# POE_plus_input.net
KiCad netlist of a schematic drawn in EAGLE
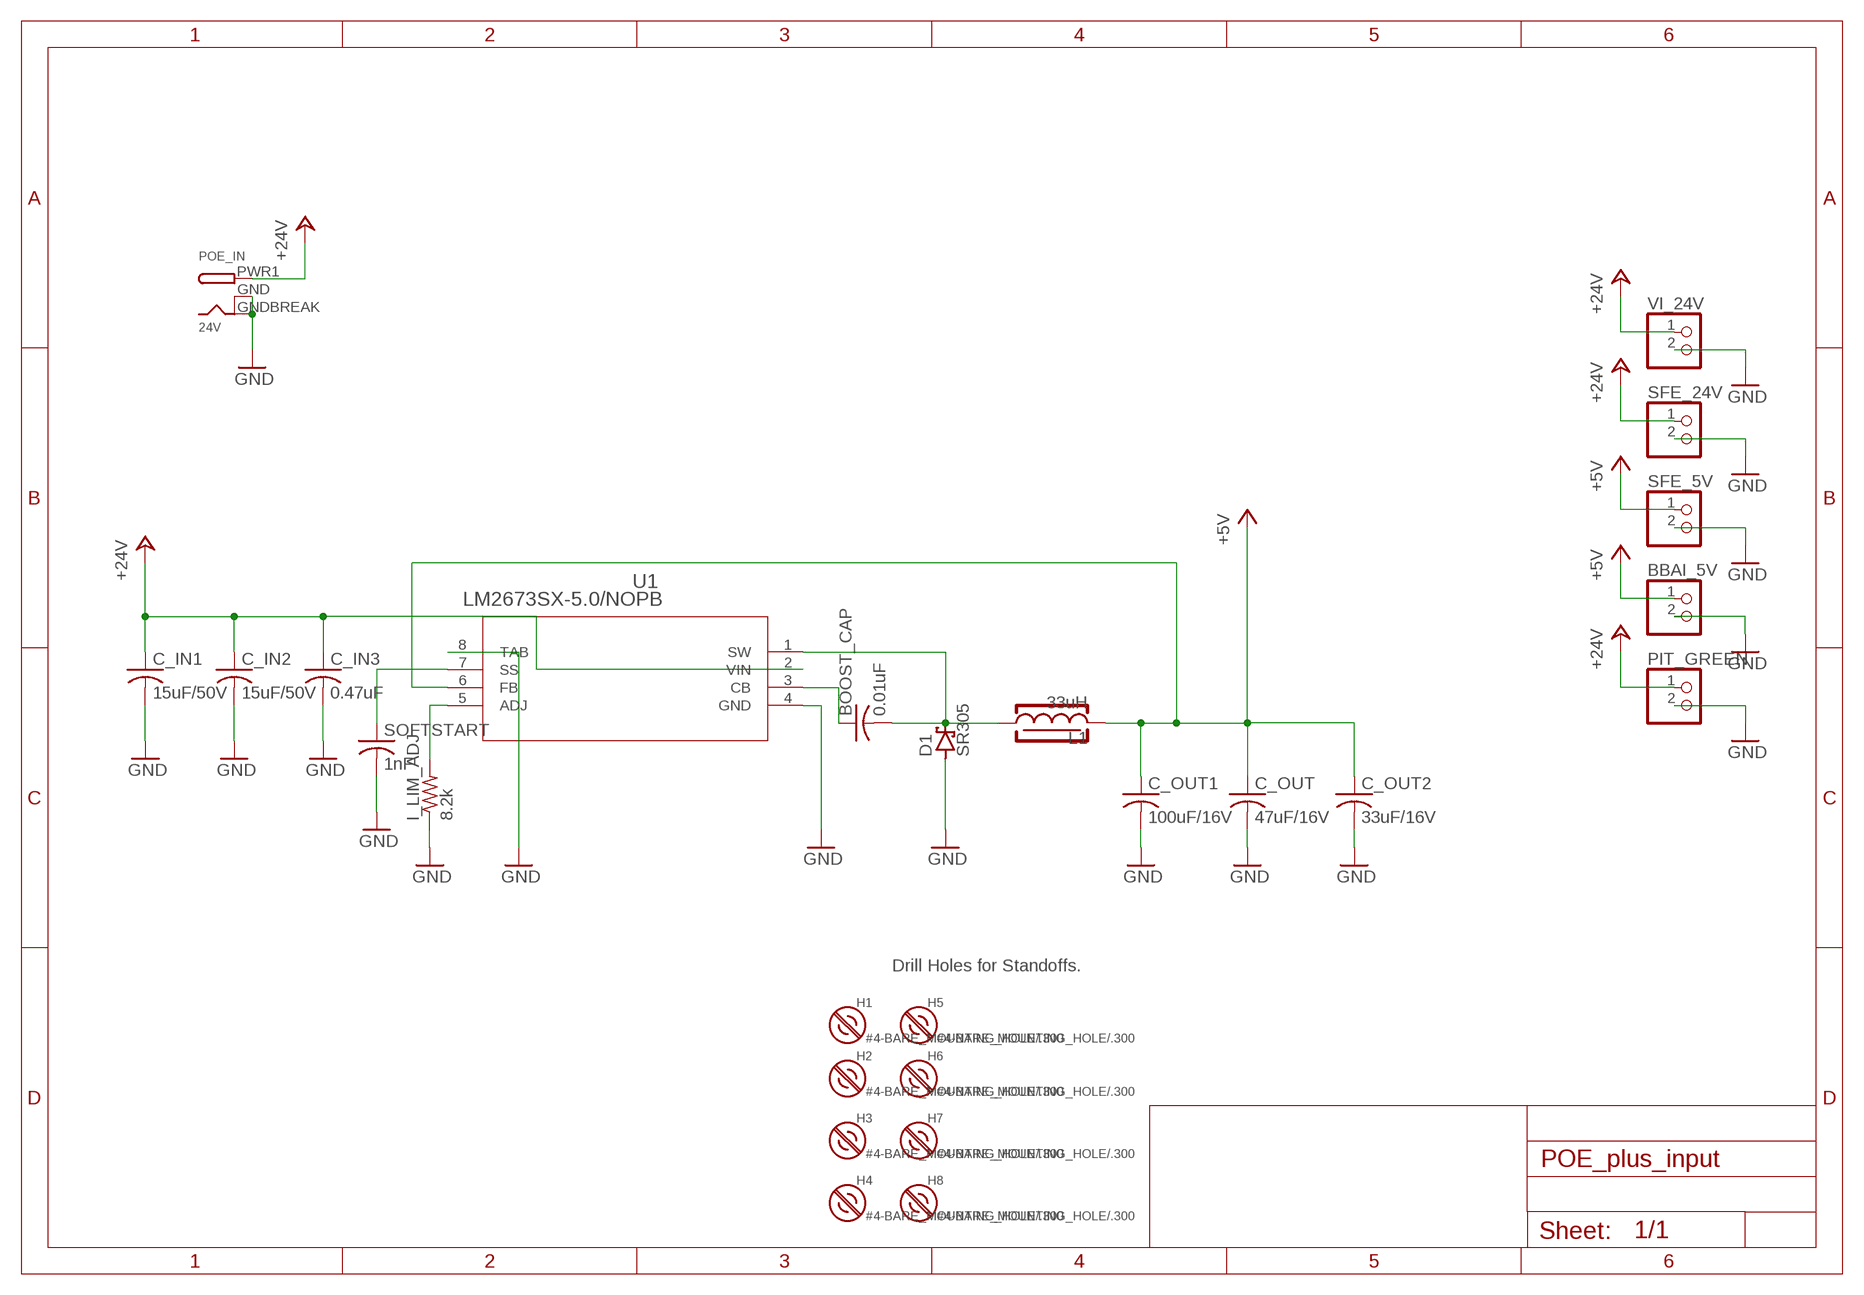
[diagram p0: schematic, sheet 1]

(export (version "E")
  (design (tool "Eeschema 10.0.6"))
  (components
    (comp (ref "BBAI_5V")
      (value "PINHD-1X2")
      (footprint "eagle-import:1X02")
      (fields (field (name "MFR") "Molex") (field (name "MPN") "1718573002"))
      (libsource (lib "eagle-import") (part "PINHD-1X2"))
    )
    (comp (ref "BOOST_CAP")
      (value "0.01uF")
      (footprint "eagle-import:C0805K")
      (fields (field (name "MFR") "AVX Corporation") (field (name "MPN") "06035C103JAT2A"))
      (libsource (lib "eagle-import") (part "C-USC0805K"))
    )
    (comp (ref "C_IN1")
      (value "15uF/50V")
      (footprint "eagle-import:C2220K")
      (fields (field (name "MFR") "United Chemi-Con") (field (name "MPN") "KTS500B156M55N0T00"))
      (libsource (lib "eagle-import") (part "C-USC2220K"))
    )
    (comp (ref "C_IN2")
      (value "15uF/50V")
      (footprint "eagle-import:C2220K")
      (fields (field (name "MFR") "United Chemi-Con") (field (name "MPN") "KTS500B156M55N0T00"))
      (libsource (lib "eagle-import") (part "C-USC2220K"))
    )
    (comp (ref "C_IN3")
      (value "0.47uF")
      (footprint "eagle-import:C0805K")
      (fields (field (name "MFR") "Taiyo Yuden") (field (name "MPN") "UMK107ABJ474KA-T"))
      (libsource (lib "eagle-import") (part "C-USC0805K"))
    )
    (comp (ref "C_OUT")
      (value "47uF/16V")
      (footprint "eagle-import:C1210K")
      (fields (field (name "MFR") "Murata Electronics") (field (name "MPN") "GRM32EC81C476KE15K"))
      (libsource (lib "eagle-import") (part "C-USC1210K"))
    )
    (comp (ref "C_OUT1")
      (value "100uF/16V")
      (footprint "eagle-import:C1210K")
      (fields (field (name "MFR") "Taiyo Yuden") (field (name "MPN") "EMK325ABJ107MM-P"))
      (libsource (lib "eagle-import") (part "C-USC1210K"))
    )
    (comp (ref "C_OUT2")
      (value "33uF/16V")
      (footprint "eagle-import:C1206K")
      (fields (field (name "MFR") "TDK Corporation") (field (name "MPN") "C3216X5R1C336M160AB"))
      (libsource (lib "eagle-import") (part "C-USC1206K"))
    )
    (comp (ref "D1")
      (value "SR305")
      (footprint "eagle-import:C4111-15")
      (fields (field (name "MFR") "Micro Commercial Co") (field (name "MPN") "SR305-TP"))
      (libsource (lib "eagle-import") (part "1N5908"))
    )
    (comp (ref "H1")
      (value "#4-BARE_MOUNTING_HOLE/.300")
      (footprint "eagle-import:#4_.300-BARE+STD_NUT_OR_STAR_WASHER")
      (libsource (lib "eagle-import") (part "#4-BARE_MOUNTING_HOLE/.300"))
    )
    (comp (ref "H2")
      (value "#4-BARE_MOUNTING_HOLE/.300")
      (footprint "eagle-import:#4_.300-BARE+STD_NUT_OR_STAR_WASHER")
      (libsource (lib "eagle-import") (part "#4-BARE_MOUNTING_HOLE/.300"))
    )
    (comp (ref "H3")
      (value "#4-BARE_MOUNTING_HOLE/.300")
      (footprint "eagle-import:#4_.300-BARE+STD_NUT_OR_STAR_WASHER")
      (libsource (lib "eagle-import") (part "#4-BARE_MOUNTING_HOLE/.300"))
    )
    (comp (ref "H4")
      (value "#4-BARE_MOUNTING_HOLE/.300")
      (footprint "eagle-import:#4_.300-BARE+STD_NUT_OR_STAR_WASHER")
      (libsource (lib "eagle-import") (part "#4-BARE_MOUNTING_HOLE/.300"))
    )
    (comp (ref "H5")
      (value "#4-BARE_MOUNTING_HOLE/.300")
      (footprint "eagle-import:#4_.300-BARE+STD_NUT_OR_STAR_WASHER")
      (libsource (lib "eagle-import") (part "#4-BARE_MOUNTING_HOLE/.300"))
    )
    (comp (ref "H6")
      (value "#4-BARE_MOUNTING_HOLE/.300")
      (footprint "eagle-import:#4_.300-BARE+STD_NUT_OR_STAR_WASHER")
      (libsource (lib "eagle-import") (part "#4-BARE_MOUNTING_HOLE/.300"))
    )
    (comp (ref "H7")
      (value "#4-BARE_MOUNTING_HOLE/.300")
      (footprint "eagle-import:#4_.300-BARE+STD_NUT_OR_STAR_WASHER")
      (libsource (lib "eagle-import") (part "#4-BARE_MOUNTING_HOLE/.300"))
    )
    (comp (ref "H8")
      (value "#4-BARE_MOUNTING_HOLE/.300")
      (footprint "eagle-import:#4_.300-BARE+STD_NUT_OR_STAR_WASHER")
      (libsource (lib "eagle-import") (part "#4-BARE_MOUNTING_HOLE/.300"))
    )
    (comp (ref "I_LIM_ADJ")
      (value "8.2k")
      (footprint "eagle-import:1206-A")
      (fields (field (name "MFR") "Yageo") (field (name "MPN") "RC1206FR-078K2L"))
      (libsource (lib "eagle-import") (part "R-US_1206-A"))
    )
    (comp (ref "L1")
      (value "33uH")
      (footprint "eagle-import:L_SHIELDED_13MMX13MMX6MM")
      (fields (field (name "MFR") "Pulse Electronics Power") (field (name "MPN") "PE-53823SNL"))
      (libsource (lib "eagle-import") (part "L_SHIELDED"))
    )
    (comp (ref "PIT_GREEN")
      (value "PINHD-1X2")
      (footprint "eagle-import:1X02")
      (fields (field (name "MFR") "Molex") (field (name "MPN") "1718573002"))
      (libsource (lib "eagle-import") (part "PINHD-1X2"))
    )
    (comp (ref "POE_IN")
      (value "24V")
      (footprint "eagle-import:DCJACK_2MM_SMT")
      (fields (field (name "MFR") "Kycon, Inc.") (field (name "MPN") "KLDX-SMT2-0202-ATR"))
      (libsource (lib "eagle-import") (part "DCBARRELSMT"))
    )
    (comp (ref "SFE_5V")
      (value "PINHD-1X2")
      (footprint "eagle-import:1X02")
      (fields (field (name "MFR") "Molex") (field (name "MPN") "1718573002"))
      (libsource (lib "eagle-import") (part "PINHD-1X2"))
    )
    (comp (ref "SFE_24V")
      (value "PINHD-1X2")
      (footprint "eagle-import:1X02")
      (fields (field (name "MFR") "Molex") (field (name "MPN") "1718573002"))
      (libsource (lib "eagle-import") (part "PINHD-1X2"))
    )
    (comp (ref "SOFTSTART")
      (value "1nF")
      (footprint "eagle-import:C0603K")
      (fields (field (name "MFR") "Samsung Electro-Mechanics") (field (name "MPN") "CL10C102JB8NNNC"))
      (libsource (lib "eagle-import") (part "C-USC0603K"))
    )
    (comp (ref "U1")
      (value "LM2673SX-5.0/NOPB")
      (footprint "eagle-import:TS7B")
      (fields (field (name "PARTNUMBER") "LM2673S-12") (field (name "MFR") "Texas Instruments"))
      (libsource (lib "eagle-import") (part "LM2673SX-5.0/NOPB"))
    )
    (comp (ref "VI_24V")
      (value "PINHD-1X2")
      (footprint "eagle-import:1X02")
      (fields (field (name "MFR") "Molex") (field (name "MPN") "1718573002"))
      (libsource (lib "eagle-import") (part "PINHD-1X2"))
    )
  )
  (nets
    (net (code "1") (name "+5V") (class "Default")
      (node (ref "BBAI_5V") (pin "1") (pinfunction "1_1") (pintype "passive"))
      (node (ref "C_OUT") (pin "1") (pinfunction "1_1") (pintype "passive"))
      (node (ref "C_OUT1") (pin "1") (pinfunction "1_1") (pintype "passive"))
      (node (ref "C_OUT2") (pin "1") (pinfunction "1_1") (pintype "passive"))
      (node (ref "L1") (pin "2") (pinfunction "2_2") (pintype "passive"))
      (node (ref "SFE_5V") (pin "1") (pinfunction "1_1") (pintype "passive"))
      (node (ref "U1") (pin "6") (pinfunction "FB_6") (pintype "passive"))
    )
    (net (code "2") (name "+24V") (class "Default")
      (node (ref "C_IN1") (pin "1") (pinfunction "1_1") (pintype "passive"))
      (node (ref "C_IN2") (pin "1") (pinfunction "1_1") (pintype "passive"))
      (node (ref "C_IN3") (pin "1") (pinfunction "1_1") (pintype "passive"))
      (node (ref "PIT_GREEN") (pin "1") (pinfunction "1_1") (pintype "passive"))
      (node (ref "POE_IN") (pin "PWR1") (pinfunction "PWR_PWR1") (pintype "power_in"))
      (node (ref "SFE_24V") (pin "1") (pinfunction "1_1") (pintype "passive"))
      (node (ref "U1") (pin "2") (pinfunction "VIN_2") (pintype "input"))
      (node (ref "VI_24V") (pin "1") (pinfunction "1_1") (pintype "passive"))
    )
    (net (code "3") (name "GND") (class "Default")
      (node (ref "BBAI_5V") (pin "2") (pinfunction "2_2") (pintype "passive"))
      (node (ref "C_IN1") (pin "2") (pinfunction "2_2") (pintype "passive"))
      (node (ref "C_IN2") (pin "2") (pinfunction "2_2") (pintype "passive"))
      (node (ref "C_IN3") (pin "2") (pinfunction "2_2") (pintype "passive"))
      (node (ref "C_OUT") (pin "2") (pinfunction "2_2") (pintype "passive"))
      (node (ref "C_OUT1") (pin "2") (pinfunction "2_2") (pintype "passive"))
      (node (ref "C_OUT2") (pin "2") (pinfunction "2_2") (pintype "passive"))
      (node (ref "D1") (pin "A") (pinfunction "A_A") (pintype "passive"))
      (node (ref "I_LIM_ADJ") (pin "1") (pinfunction "1_1") (pintype "passive"))
      (node (ref "PIT_GREEN") (pin "2") (pinfunction "2_2") (pintype "passive"))
      (node (ref "POE_IN") (pin "GND") (pinfunction "GNDBREAK_GND") (pintype "power_in"))
      (node (ref "POE_IN") (pin "GNDBREAK") (pinfunction "GND_GNDBREAK") (pintype "power_in"))
      (node (ref "SFE_24V") (pin "2") (pinfunction "2_2") (pintype "passive"))
      (node (ref "SFE_5V") (pin "2") (pinfunction "2_2") (pintype "passive"))
      (node (ref "SOFTSTART") (pin "2") (pinfunction "2_2") (pintype "passive"))
      (node (ref "U1") (pin "4") (pinfunction "GND_4") (pintype "passive"))
      (node (ref "U1") (pin "8") (pinfunction "TAB_8") (pintype "passive"))
      (node (ref "VI_24V") (pin "2") (pinfunction "2_2") (pintype "passive"))
    )
    (net (code "4") (name "Net-(U1-ADJ)") (class "Default")
      (node (ref "I_LIM_ADJ") (pin "2") (pinfunction "2_2") (pintype "passive"))
      (node (ref "U1") (pin "5") (pinfunction "ADJ_5") (pintype "passive"))
    )
    (net (code "5") (name "Net-(U1-CB)") (class "Default")
      (node (ref "BOOST_CAP") (pin "1") (pinfunction "1_1") (pintype "passive"))
      (node (ref "U1") (pin "3") (pinfunction "CB_3") (pintype "passive"))
    )
    (net (code "6") (name "Net-(U1-SS)") (class "Default")
      (node (ref "SOFTSTART") (pin "1") (pinfunction "1_1") (pintype "passive"))
      (node (ref "U1") (pin "7") (pinfunction "SS_7") (pintype "passive"))
    )
    (net (code "7") (name "Net-(U1-SW)") (class "Default")
      (node (ref "BOOST_CAP") (pin "2") (pinfunction "2_2") (pintype "passive"))
      (node (ref "D1") (pin "C") (pinfunction "C_C") (pintype "passive"))
      (node (ref "L1") (pin "1") (pinfunction "1_1") (pintype "passive"))
      (node (ref "U1") (pin "1") (pinfunction "SW_1") (pintype "output"))
    )
  )
)
